# Lab1_Lyaptsev_main.net
KiCad netlist of a schematic drawn in Altium Designer
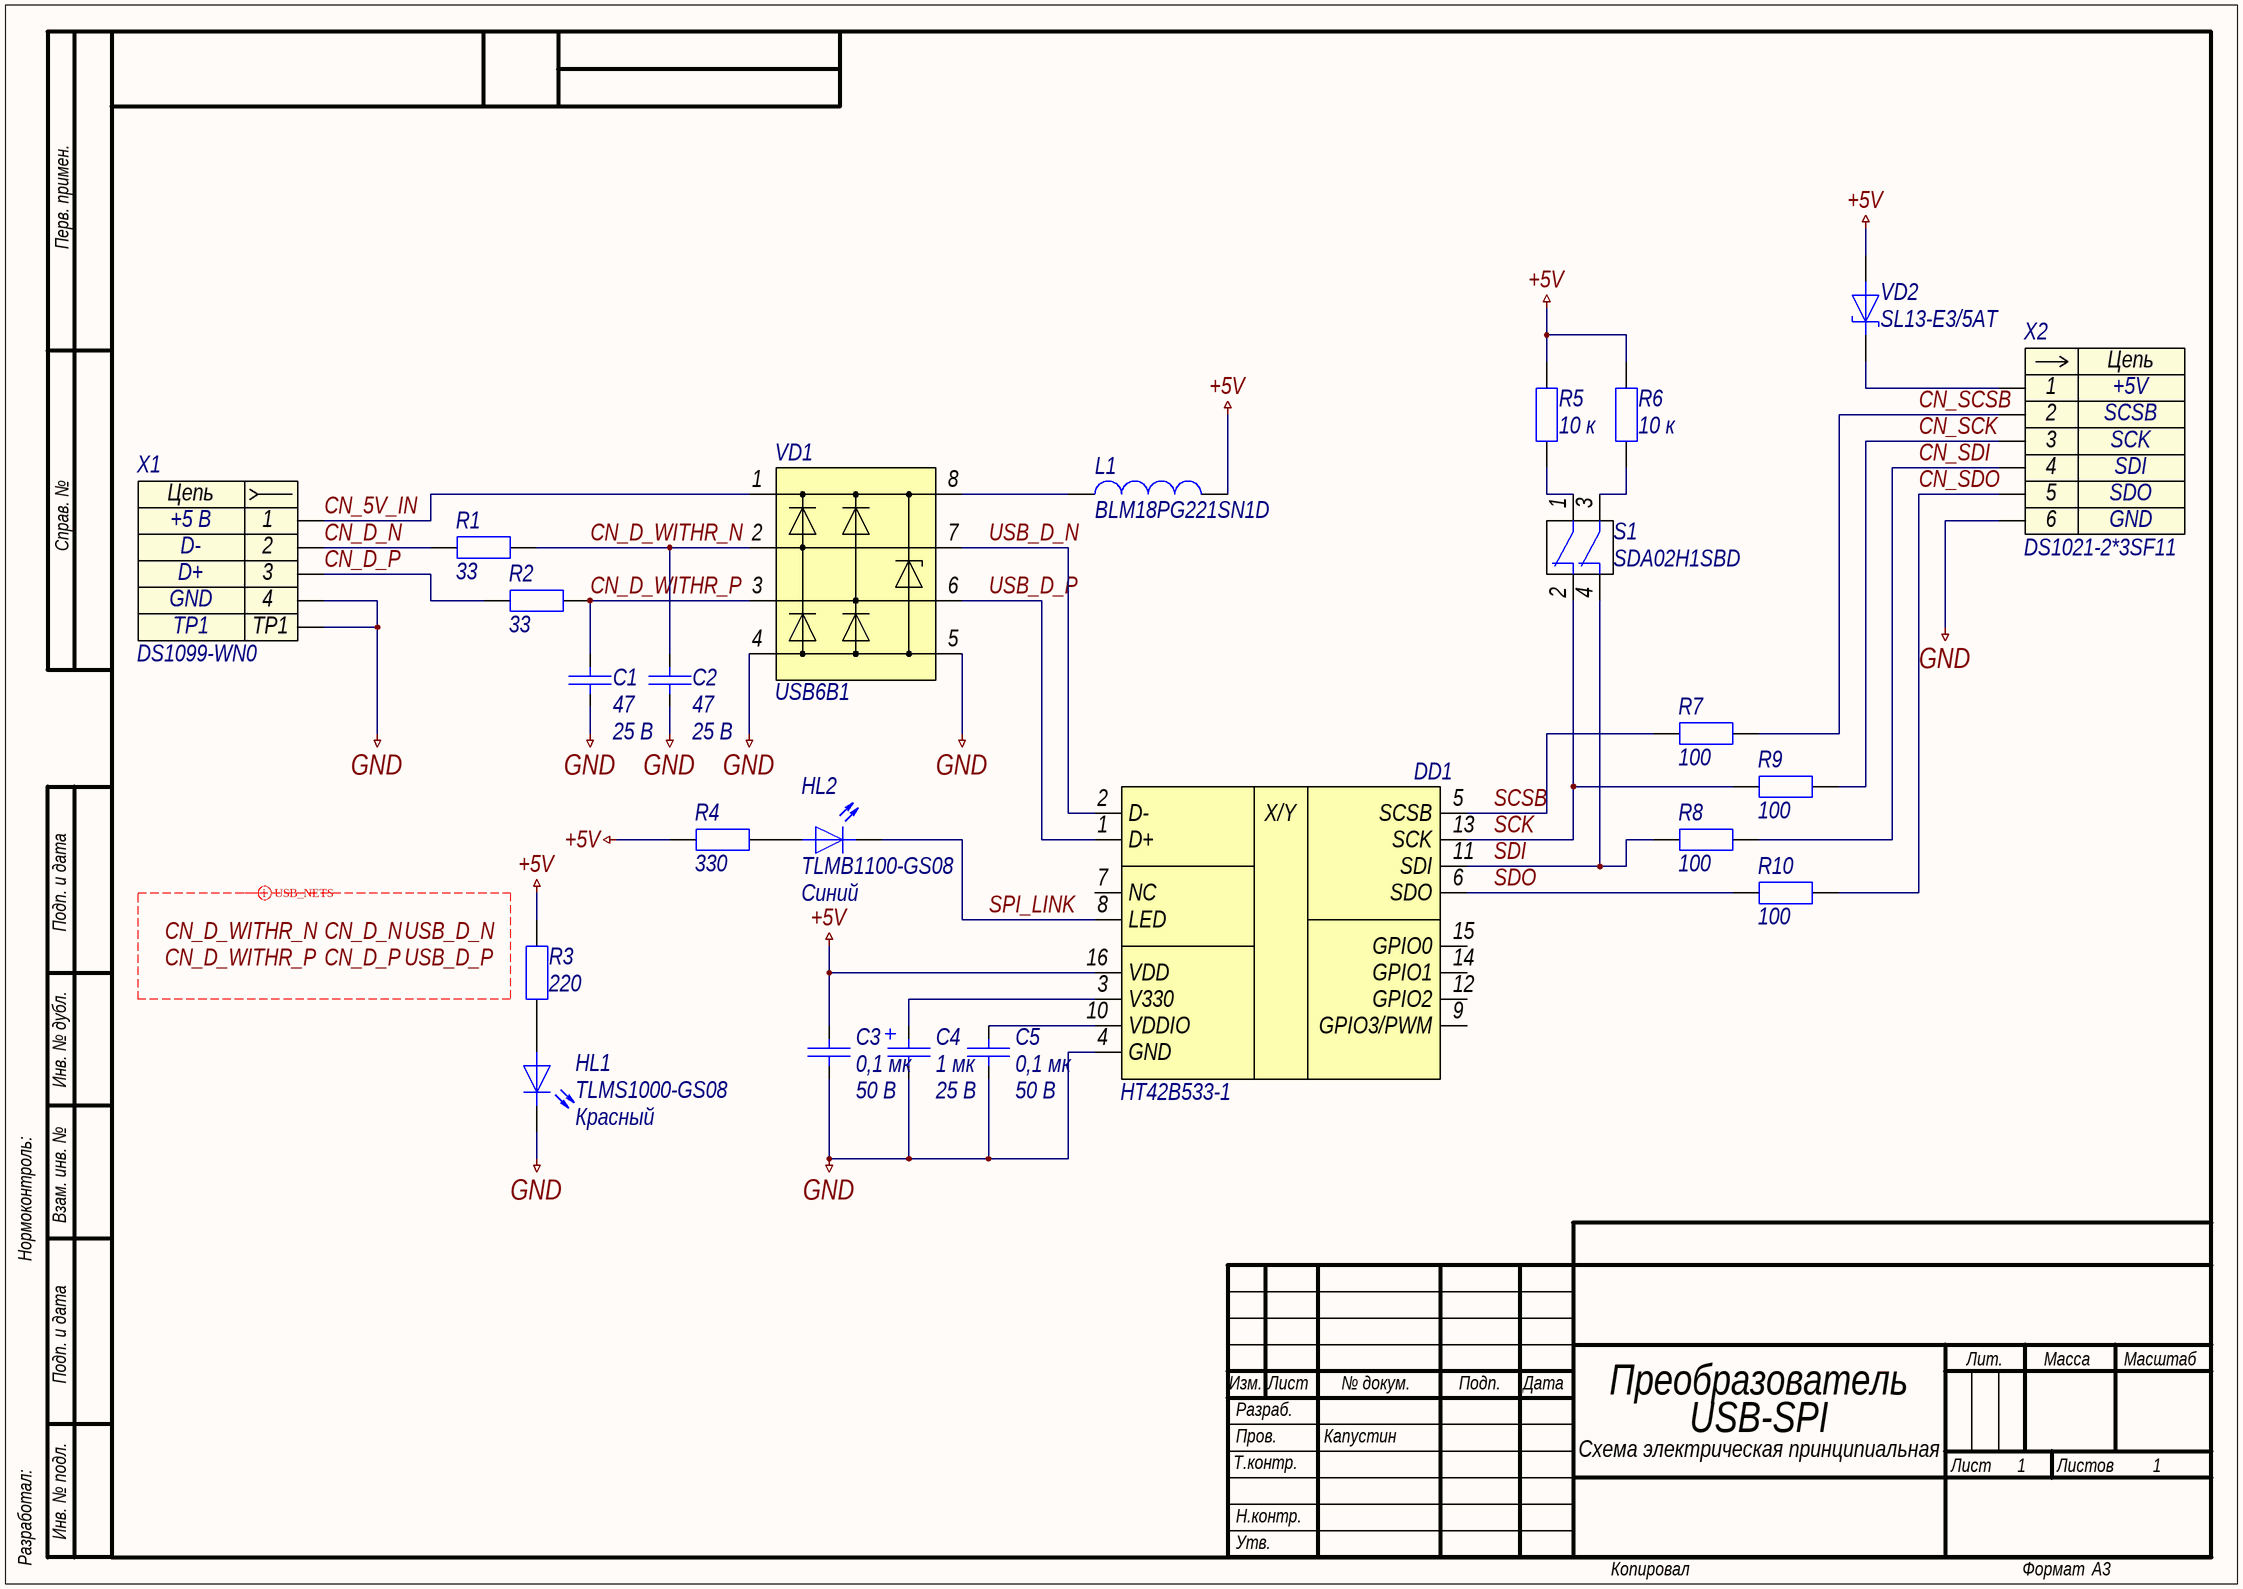
[diagram p0: Lab1_Lyaptsev_main.schdoc]

(export (version "E")
  (design (tool "Eeschema 10.0.6"))
  (components
    (comp (ref "C1")
      (value "47")
      (footprint "C0201")
      (description "=Описание")
      (fields (field (name "НАПРЯЖЕНИЕ") "25 В"))
      (libsource (lib "Database_Students") (part "CAPACITOR-NONPOLAR"))
    )
    (comp (ref "C2")
      (value "47")
      (footprint "C0201")
      (description "=Описание")
      (fields (field (name "НАПРЯЖЕНИЕ") "25 В"))
      (libsource (lib "Database_Students") (part "CAPACITOR-NONPOLAR"))
    )
    (comp (ref "C3")
      (value "0,1 мк")
      (footprint "C0603")
      (description "=Описание")
      (fields (field (name "НАПРЯЖЕНИЕ") "50 В"))
      (libsource (lib "Database_Students") (part "CAPACITOR-NONPOLAR"))
    )
    (comp (ref "C4")
      (value "1 мк")
      (footprint "C1206POLAR")
      (description "=Описание")
      (fields (field (name "НАПРЯЖЕНИЕ") "25 В"))
      (libsource (lib "Database_Students") (part "CAPACITOR-POLAR"))
    )
    (comp (ref "C5")
      (value "0,1 мк")
      (footprint "C0603")
      (description "=Описание")
      (fields (field (name "НАПРЯЖЕНИЕ") "50 В"))
      (libsource (lib "Database_Students") (part "CAPACITOR-NONPOLAR"))
    )
    (comp (ref "DD1")
      (value "HT42B533-1")
      (footprint "NSOP-16")
      (description "=Описание")
      (libsource (lib "Database_Students") (part "HT42B533-1"))
    )
    (comp (ref "HL1")
      (value "TLMS1000-GS08")
      (footprint "HL0603")
      (description "=Описание")
      (fields (field (name "COLOUR") "Красный"))
      (libsource (lib "Database_Students") (part "LED-COMMON"))
    )
    (comp (ref "HL2")
      (value "TLMB1100-GS08")
      (footprint "HL0603")
      (description "=Описание")
      (fields (field (name "COLOUR") "Синий"))
      (libsource (lib "Database_Students") (part "LED-COMMON"))
    )
    (comp (ref "L1")
      (value "BLM18PG221SN1D")
      (footprint "BLM-2-0603")
      (description "=Описание")
      (libsource (lib "Database_Students") (part "FERRITE-BEAD"))
    )
    (comp (ref "R1")
      (value "33")
      (footprint "R0603")
      (description "=Описание")
      (libsource (lib "Database_Students") (part "R-COMMON"))
    )
    (comp (ref "R2")
      (value "33")
      (footprint "R0603")
      (description "=Описание")
      (libsource (lib "Database_Students") (part "R-COMMON"))
    )
    (comp (ref "R3")
      (value "220")
      (footprint "R0603")
      (description "=Описание")
      (libsource (lib "Database_Students") (part "R-COMMON"))
    )
    (comp (ref "R4")
      (value "330")
      (footprint "R0603")
      (description "=Описание")
      (libsource (lib "Database_Students") (part "R-COMMON"))
    )
    (comp (ref "R5")
      (value "10 к")
      (footprint "R0603")
      (description "=Описание")
      (libsource (lib "Database_Students") (part "R-COMMON"))
    )
    (comp (ref "R6")
      (value "10 к")
      (footprint "R0603")
      (description "=Описание")
      (libsource (lib "Database_Students") (part "R-COMMON"))
    )
    (comp (ref "R7")
      (value "100")
      (footprint "R0603")
      (description "=Описание")
      (libsource (lib "Database_Students") (part "R-COMMON"))
    )
    (comp (ref "R8")
      (value "100")
      (footprint "R0603")
      (description "=Описание")
      (libsource (lib "Database_Students") (part "R-COMMON"))
    )
    (comp (ref "R9")
      (value "100")
      (footprint "R0603")
      (description "=Описание")
      (libsource (lib "Database_Students") (part "R-COMMON"))
    )
    (comp (ref "R10")
      (value "100")
      (footprint "R0603")
      (description "=Описание")
      (libsource (lib "Database_Students") (part "R-COMMON"))
    )
    (comp (ref "S1")
      (value "SDA02H1SBD")
      (footprint "SDA02H1SBD")
      (description "=Описание")
      (libsource (lib "Database_Students") (part "SWITCH-4C"))
    )
    (comp (ref "VD1")
      (value "USB6B1")
      (footprint "SOIC-8")
      (description "=Описание")
      (libsource (lib "Database_Students") (part "USB6B1"))
    )
    (comp (ref "VD2")
      (value "SL13-E3/5AT")
      (footprint "DO-214AC")
      (description "=Описание")
      (libsource (lib "Database_Students") (part "DIODE-SCHOTTKY"))
    )
    (comp (ref "X1")
      (value "DS1099-WN0")
      (footprint "DS1099-WN0")
      (description "=Описание")
      (libsource (lib "Database_Students") (part "HEADER-4-TP1-SCT"))
    )
    (comp (ref "X2")
      (value "DS1021-2*3SF11")
      (footprint "DS1021-2X3SF11")
      (libsource (lib "Database_Students") (part "HEADER-6-PLG"))
    )
  )
  (nets
    (net (code "1") (name "+5V") (class "Default")
      (node (ref "C3") (pin "1") (pinfunction "1_1") (pintype "passive"))
      (node (ref "DD1") (pin "16") (pinfunction "VDD_16") (pintype "passive"))
      (node (ref "L1") (pin "2") (pinfunction "2_2") (pintype "passive"))
      (node (ref "R3") (pin "2") (pinfunction "2_2") (pintype "passive"))
      (node (ref "R4") (pin "1") (pinfunction "1_1") (pintype "passive"))
      (node (ref "R5") (pin "2") (pinfunction "2_2") (pintype "passive"))
      (node (ref "R6") (pin "2") (pinfunction "2_2") (pintype "passive"))
      (node (ref "VD2") (pin "2") (pinfunction "2_2") (pintype "passive"))
    )
    (net (code "2") (name "/CN_5V_IN") (class "Default")
      (node (ref "VD1") (pin "1") (pinfunction "1_1") (pintype "passive"))
      (node (ref "X1") (pin "1") (pinfunction "1_1") (pintype "passive"))
    )
    (net (code "3") (name "/CN_D_N") (class "Default")
      (node (ref "R1") (pin "1") (pinfunction "1_1") (pintype "passive"))
      (node (ref "X1") (pin "2") (pinfunction "2_2") (pintype "passive"))
    )
    (net (code "4") (name "/CN_D_P") (class "Default")
      (node (ref "R2") (pin "1") (pinfunction "1_1") (pintype "passive"))
      (node (ref "X1") (pin "3") (pinfunction "3_3") (pintype "passive"))
    )
    (net (code "5") (name "/CN_D_WITHR_N") (class "Default")
      (node (ref "C2") (pin "1") (pinfunction "1_1") (pintype "passive"))
      (node (ref "R1") (pin "2") (pinfunction "2_2") (pintype "passive"))
      (node (ref "VD1") (pin "2") (pinfunction "2_2") (pintype "passive"))
    )
    (net (code "6") (name "/CN_D_WITHR_P") (class "Default")
      (node (ref "C1") (pin "1") (pinfunction "1_1") (pintype "passive"))
      (node (ref "R2") (pin "2") (pinfunction "2_2") (pintype "passive"))
      (node (ref "VD1") (pin "3") (pinfunction "3_3") (pintype "passive"))
    )
    (net (code "7") (name "/CN_SCK") (class "Default")
      (node (ref "R9") (pin "2") (pinfunction "2_2") (pintype "passive"))
      (node (ref "X2") (pin "3") (pinfunction "3_3") (pintype "passive"))
    )
    (net (code "8") (name "/CN_SCSB") (class "Default")
      (node (ref "R7") (pin "2") (pinfunction "2_2") (pintype "passive"))
      (node (ref "X2") (pin "2") (pinfunction "2_2") (pintype "passive"))
    )
    (net (code "9") (name "/CN_SDI") (class "Default")
      (node (ref "R8") (pin "2") (pinfunction "2_2") (pintype "passive"))
      (node (ref "X2") (pin "4") (pinfunction "4_4") (pintype "passive"))
    )
    (net (code "10") (name "/CN_SDO") (class "Default")
      (node (ref "R10") (pin "2") (pinfunction "2_2") (pintype "passive"))
      (node (ref "X2") (pin "5") (pinfunction "5_5") (pintype "passive"))
    )
    (net (code "11") (name "/SCK") (class "Default")
      (node (ref "DD1") (pin "13") (pinfunction "SCK_13") (pintype "passive"))
      (node (ref "R9") (pin "1") (pinfunction "1_1") (pintype "passive"))
      (node (ref "S1") (pin "2") (pinfunction "2_2") (pintype "passive"))
    )
    (net (code "12") (name "/SCSB") (class "Default")
      (node (ref "DD1") (pin "5") (pinfunction "SCSB_5") (pintype "passive"))
      (node (ref "R7") (pin "1") (pinfunction "1_1") (pintype "passive"))
    )
    (net (code "13") (name "/SDI") (class "Default")
      (node (ref "DD1") (pin "11") (pinfunction "SDI_11") (pintype "passive"))
      (node (ref "R8") (pin "1") (pinfunction "1_1") (pintype "passive"))
      (node (ref "S1") (pin "4") (pinfunction "4_4") (pintype "passive"))
    )
    (net (code "14") (name "/SDO") (class "Default")
      (node (ref "DD1") (pin "6") (pinfunction "SDO_6") (pintype "passive"))
      (node (ref "R10") (pin "1") (pinfunction "1_1") (pintype "passive"))
    )
    (net (code "15") (name "/SPI_LINK") (class "Default")
      (node (ref "DD1") (pin "8") (pinfunction "LED_8") (pintype "passive"))
      (node (ref "HL2") (pin "1") (pinfunction "1_1") (pintype "passive"))
    )
    (net (code "16") (name "/USB_D_N") (class "Default")
      (node (ref "DD1") (pin "2") (pinfunction "D-_2") (pintype "passive"))
      (node (ref "VD1") (pin "7") (pinfunction "7_7") (pintype "passive"))
    )
    (net (code "17") (name "/USB_D_P") (class "Default")
      (node (ref "DD1") (pin "1") (pinfunction "D+_1") (pintype "passive"))
      (node (ref "VD1") (pin "6") (pinfunction "6_6") (pintype "passive"))
    )
    (net (code "18") (name "GND") (class "Default")
      (node (ref "C1") (pin "2") (pinfunction "2_2") (pintype "passive"))
      (node (ref "C2") (pin "2") (pinfunction "2_2") (pintype "passive"))
      (node (ref "C3") (pin "2") (pinfunction "2_2") (pintype "passive"))
      (node (ref "C4") (pin "2") (pinfunction "2_2") (pintype "passive"))
      (node (ref "C5") (pin "2") (pinfunction "2_2") (pintype "passive"))
      (node (ref "DD1") (pin "4") (pinfunction "GND_4") (pintype "passive"))
      (node (ref "HL1") (pin "1") (pinfunction "1_1") (pintype "passive"))
      (node (ref "VD1") (pin "4") (pinfunction "4_4") (pintype "passive"))
      (node (ref "VD1") (pin "5") (pinfunction "5_5") (pintype "passive"))
      (node (ref "X1") (pin "4") (pinfunction "4_4") (pintype "passive"))
      (node (ref "X1") (pin "TP1") (pinfunction "TP1_TP1") (pintype "passive"))
      (node (ref "X2") (pin "6") (pinfunction "6_6") (pintype "passive"))
    )
    (net (code "19") (name "Net-(DD1-V330)") (class "Default")
      (node (ref "C4") (pin "1") (pinfunction "1_1") (pintype "passive"))
      (node (ref "DD1") (pin "3") (pinfunction "V330_3") (pintype "passive"))
    )
    (net (code "20") (name "Net-(DD1-VDDIO)") (class "Default")
      (node (ref "C5") (pin "1") (pinfunction "1_1") (pintype "passive"))
      (node (ref "DD1") (pin "10") (pinfunction "VDDIO_10") (pintype "passive"))
    )
    (net (code "21") (name "Net-(HL1-Pad2)") (class "Default")
      (node (ref "HL1") (pin "2") (pinfunction "2_2") (pintype "passive"))
      (node (ref "R3") (pin "1") (pinfunction "1_1") (pintype "passive"))
    )
    (net (code "22") (name "Net-(HL2-Pad2)") (class "Default")
      (node (ref "HL2") (pin "2") (pinfunction "2_2") (pintype "passive"))
      (node (ref "R4") (pin "2") (pinfunction "2_2") (pintype "passive"))
    )
    (net (code "23") (name "Net-(L1-Pad1)") (class "Default")
      (node (ref "L1") (pin "1") (pinfunction "1_1") (pintype "passive"))
      (node (ref "VD1") (pin "8") (pinfunction "8_8") (pintype "passive"))
    )
    (net (code "24") (name "Net-(R5-Pad1)") (class "Default")
      (node (ref "R5") (pin "1") (pinfunction "1_1") (pintype "passive"))
      (node (ref "S1") (pin "1") (pinfunction "1_1") (pintype "passive"))
    )
    (net (code "25") (name "Net-(R6-Pad1)") (class "Default")
      (node (ref "R6") (pin "1") (pinfunction "1_1") (pintype "passive"))
      (node (ref "S1") (pin "3") (pinfunction "3_3") (pintype "passive"))
    )
    (net (code "26") (name "Net-(VD2-Pad1)") (class "Default")
      (node (ref "VD2") (pin "1") (pinfunction "1_1") (pintype "passive"))
      (node (ref "X2") (pin "1") (pinfunction "1_1") (pintype "passive"))
    )
    (net (code "27") (name "unconnected-(DD1-GPIO0-Pad15)") (class "Default")
      (node (ref "DD1") (pin "15") (pinfunction "GPIO0_15") (pintype "passive"))
    )
    (net (code "28") (name "unconnected-(DD1-GPIO1-Pad14)") (class "Default")
      (node (ref "DD1") (pin "14") (pinfunction "GPIO1_14") (pintype "passive"))
    )
    (net (code "29") (name "unconnected-(DD1-GPIO2-Pad12)") (class "Default")
      (node (ref "DD1") (pin "12") (pinfunction "GPIO2_12") (pintype "passive"))
    )
    (net (code "30") (name "unconnected-(DD1-GPIO3{slash}PWM-Pad9)") (class "Default")
      (node (ref "DD1") (pin "9") (pinfunction "GPIO3/PWM_9") (pintype "passive"))
    )
    (net (code "31") (name "unconnected-(DD1-NC-Pad7)") (class "Default")
      (node (ref "DD1") (pin "7") (pinfunction "NC_7") (pintype "passive"))
    )
  )
)
